# BOOST.net
KiCad netlist of a schematic drawn in Altium Designer
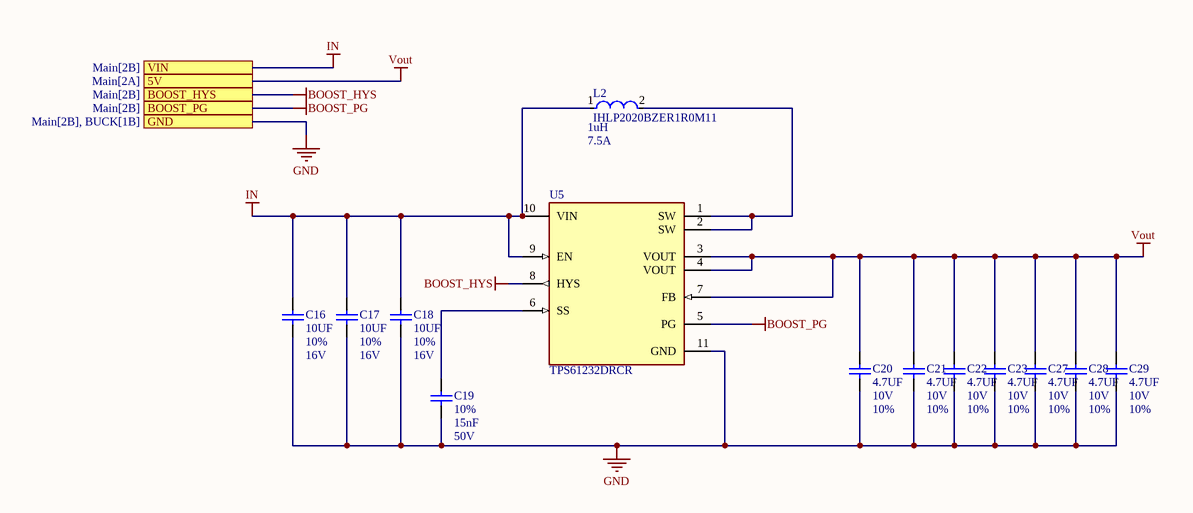
[diagram p0: BOOST.SchDoc]

(export (version "E")
  (design (tool "Eeschema 10.0.6"))
  (components
    (comp (ref "C16")
      (value "10UF")
      (footprint "1206_CAP")
      (description "Capacitor Surface Mount 1206 Footprint 10UF 16V 10% Tolerance Ceramic X7R")
      (fields
        (field (name "MANUFACTURER") "Various")
        (field (name "TOLERANCE") "10%")
        (field (name "VOLTAGE") "16V")
        (field (name "Comment") "CAP 1206 10UF 16V 10% X7R")
      )
      (libsource (lib "University of Pennsylvania (ESE)") (part "cap"))
    )
    (comp (ref "C17")
      (value "10UF")
      (footprint "1206_CAP")
      (description "Capacitor Surface Mount 1206 Footprint 10UF 16V 10% Tolerance Ceramic X7R")
      (fields
        (field (name "MANUFACTURER") "Various")
        (field (name "TOLERANCE") "10%")
        (field (name "VOLTAGE") "16V")
        (field (name "Comment") "CAP 1206 10UF 16V 10% X7R")
      )
      (libsource (lib "University of Pennsylvania (ESE)") (part "cap"))
    )
    (comp (ref "C18")
      (value "10UF")
      (footprint "1206_CAP")
      (description "Capacitor Surface Mount 1206 Footprint 10UF 16V 10% Tolerance Ceramic X7R")
      (fields
        (field (name "MANUFACTURER") "Various")
        (field (name "TOLERANCE") "10%")
        (field (name "VOLTAGE") "16V")
        (field (name "Comment") "CAP 1206 10UF 16V 10% X7R")
      )
      (libsource (lib "University of Pennsylvania (ESE)") (part "cap"))
    )
    (comp (ref "C19")
      (value "15nF")
      (footprint "0603_CAP")
      (description "Capacitor Surface Mount 0603 Footprint 1500PF 50V 10% Tolerance Ceramic X7R")
      (fields
        (field (name "TOLERANCE") "10%")
        (field (name "MANUFACTURER") "Various")
        (field (name "VOLTAGE") "50V")
        (field (name "Comment") "CAP 0603 1500PF 50V 10% X7R")
      )
      (libsource (lib "University of Pennsylvania (ESE)") (part "cap"))
    )
    (comp (ref "C20")
      (value "4.7UF")
      (footprint "0603_CAP")
      (description "Capacitor Surface Mount 0603 Footprint 4.7UF 10V 10% Tolerance Ceramic X5R")
      (fields
        (field (name "MANUFACTURER") "Various")
        (field (name "VOLTAGE") "10V")
        (field (name "TOLERANCE") "10%")
        (field (name "Comment") "CAP 0603 4.7UF 10V 10% X5R")
      )
      (libsource (lib "University of Pennsylvania (ESE)") (part "cap"))
    )
    (comp (ref "C21")
      (value "4.7UF")
      (footprint "0603_CAP")
      (description "Capacitor Surface Mount 0603 Footprint 4.7UF 10V 10% Tolerance Ceramic X5R")
      (fields
        (field (name "MANUFACTURER") "Various")
        (field (name "VOLTAGE") "10V")
        (field (name "TOLERANCE") "10%")
        (field (name "Comment") "CAP 0603 4.7UF 10V 10% X5R")
      )
      (libsource (lib "University of Pennsylvania (ESE)") (part "cap"))
    )
    (comp (ref "C22")
      (value "4.7UF")
      (footprint "0603_CAP")
      (description "Capacitor Surface Mount 0603 Footprint 4.7UF 10V 10% Tolerance Ceramic X5R")
      (fields
        (field (name "MANUFACTURER") "Various")
        (field (name "VOLTAGE") "10V")
        (field (name "TOLERANCE") "10%")
        (field (name "Comment") "CAP 0603 4.7UF 10V 10% X5R")
      )
      (libsource (lib "University of Pennsylvania (ESE)") (part "cap"))
    )
    (comp (ref "C23")
      (value "4.7UF")
      (footprint "0603_CAP")
      (description "Capacitor Surface Mount 0603 Footprint 4.7UF 10V 10% Tolerance Ceramic X5R")
      (fields
        (field (name "MANUFACTURER") "Various")
        (field (name "VOLTAGE") "10V")
        (field (name "TOLERANCE") "10%")
        (field (name "Comment") "CAP 0603 4.7UF 10V 10% X5R")
      )
      (libsource (lib "University of Pennsylvania (ESE)") (part "cap"))
    )
    (comp (ref "C27")
      (value "4.7UF")
      (footprint "0603_CAP")
      (description "Capacitor Surface Mount 0603 Footprint 4.7UF 10V 10% Tolerance Ceramic X5R")
      (fields
        (field (name "MANUFACTURER") "Various")
        (field (name "VOLTAGE") "10V")
        (field (name "TOLERANCE") "10%")
        (field (name "Comment") "CAP 0603 4.7UF 10V 10% X5R")
      )
      (libsource (lib "University of Pennsylvania (ESE)") (part "cap"))
    )
    (comp (ref "C28")
      (value "4.7UF")
      (footprint "0603_CAP")
      (description "Capacitor Surface Mount 0603 Footprint 4.7UF 10V 10% Tolerance Ceramic X5R")
      (fields
        (field (name "MANUFACTURER") "Various")
        (field (name "VOLTAGE") "10V")
        (field (name "TOLERANCE") "10%")
        (field (name "Comment") "CAP 0603 4.7UF 10V 10% X5R")
      )
      (libsource (lib "University of Pennsylvania (ESE)") (part "cap"))
    )
    (comp (ref "C29")
      (value "4.7UF")
      (footprint "0603_CAP")
      (description "Capacitor Surface Mount 0603 Footprint 4.7UF 10V 10% Tolerance Ceramic X5R")
      (fields
        (field (name "MANUFACTURER") "Various")
        (field (name "VOLTAGE") "10V")
        (field (name "TOLERANCE") "10%")
        (field (name "Comment") "CAP 0603 4.7UF 10V 10% X5R")
      )
      (libsource (lib "University of Pennsylvania (ESE)") (part "cap"))
    )
    (comp (ref "L2")
      (value "IHLP2020BZER1R0M11")
      (footprint "FP-IHLP-2020BZ-FP_1_905x2-MFG")
      (description "Fixed Inductors Commercial Low DCR Series 1uH 7.5A 18.1mΩ 20%")
      (fields
        (field (name "CURRENT RATING") "7.5A")
        (field (name "TOLERANCE") "20%")
        (field (name "INDUCTANCE") "1uH")
      )
      (libsource (lib "Altium Content Vault") (part "725321dda6339637d4d059423bc1c3c"))
    )
    (comp (ref "U5")
      (value "TPS61232DRCR")
      (footprint "FP-DRC0010G-IPC_A")
      (description "IC REG BOOST 5V 4A 10VSON")
      (libsource (lib "Altium Content Vault") (part "8621758fd3f97d880572d390e314e8c"))
    )
  )
  (nets
    (net (code "1") (name "BOOST_HYS") (class "Default")
      (node (ref "U5") (pin "8") (pinfunction "HYS_8") (pintype "output"))
    )
    (net (code "2") (name "BOOST_PG") (class "Default")
      (node (ref "U5") (pin "5") (pinfunction "PG_5") (pintype "open_collector"))
    )
    (net (code "3") (name "GND") (class "Default")
      (node (ref "C16") (pin "1") (pinfunction "1_1") (pintype "passive"))
      (node (ref "C17") (pin "1") (pinfunction "1_1") (pintype "passive"))
      (node (ref "C18") (pin "1") (pinfunction "1_1") (pintype "passive"))
      (node (ref "C19") (pin "1") (pinfunction "1_1") (pintype "passive"))
      (node (ref "C20") (pin "1") (pinfunction "1_1") (pintype "passive"))
      (node (ref "C21") (pin "1") (pinfunction "1_1") (pintype "passive"))
      (node (ref "C22") (pin "1") (pinfunction "1_1") (pintype "passive"))
      (node (ref "C23") (pin "1") (pinfunction "1_1") (pintype "passive"))
      (node (ref "C27") (pin "1") (pinfunction "1_1") (pintype "passive"))
      (node (ref "C28") (pin "1") (pinfunction "1_1") (pintype "passive"))
      (node (ref "C29") (pin "1") (pinfunction "1_1") (pintype "passive"))
      (node (ref "U5") (pin "11") (pinfunction "GND_11") (pintype "power_in"))
    )
    (net (code "4") (name "IN") (class "Default")
      (node (ref "C16") (pin "2") (pinfunction "2_2") (pintype "passive"))
      (node (ref "C17") (pin "2") (pinfunction "2_2") (pintype "passive"))
      (node (ref "C18") (pin "2") (pinfunction "2_2") (pintype "passive"))
      (node (ref "L2") (pin "1") (pinfunction "1_1") (pintype "passive"))
      (node (ref "U5") (pin "10") (pinfunction "VIN_10") (pintype "power_in"))
      (node (ref "U5") (pin "9") (pinfunction "EN_9") (pintype "input"))
    )
    (net (code "5") (name "Net-(L2-Pad2)") (class "Default")
      (node (ref "L2") (pin "2") (pinfunction "2_2") (pintype "passive"))
      (node (ref "U5") (pin "1") (pinfunction "SW_1") (pintype "power_in"))
      (node (ref "U5") (pin "2") (pinfunction "SW_2") (pintype "power_in"))
    )
    (net (code "6") (name "Net-(U5-SS)") (class "Default")
      (node (ref "C19") (pin "2") (pinfunction "2_2") (pintype "passive"))
      (node (ref "U5") (pin "6") (pinfunction "SS_6") (pintype "input"))
    )
    (net (code "7") (name "Vout") (class "Default")
      (node (ref "C20") (pin "2") (pinfunction "2_2") (pintype "passive"))
      (node (ref "C21") (pin "2") (pinfunction "2_2") (pintype "passive"))
      (node (ref "C22") (pin "2") (pinfunction "2_2") (pintype "passive"))
      (node (ref "C23") (pin "2") (pinfunction "2_2") (pintype "passive"))
      (node (ref "C27") (pin "2") (pinfunction "2_2") (pintype "passive"))
      (node (ref "C28") (pin "2") (pinfunction "2_2") (pintype "passive"))
      (node (ref "C29") (pin "2") (pinfunction "2_2") (pintype "passive"))
      (node (ref "U5") (pin "3") (pinfunction "VOUT_3") (pintype "passive"))
      (node (ref "U5") (pin "4") (pinfunction "VOUT_4") (pintype "passive"))
      (node (ref "U5") (pin "7") (pinfunction "FB_7") (pintype "input"))
    )
  )
)
